# S4QX11.net
KiCad netlist of a schematic drawn in EAGLE
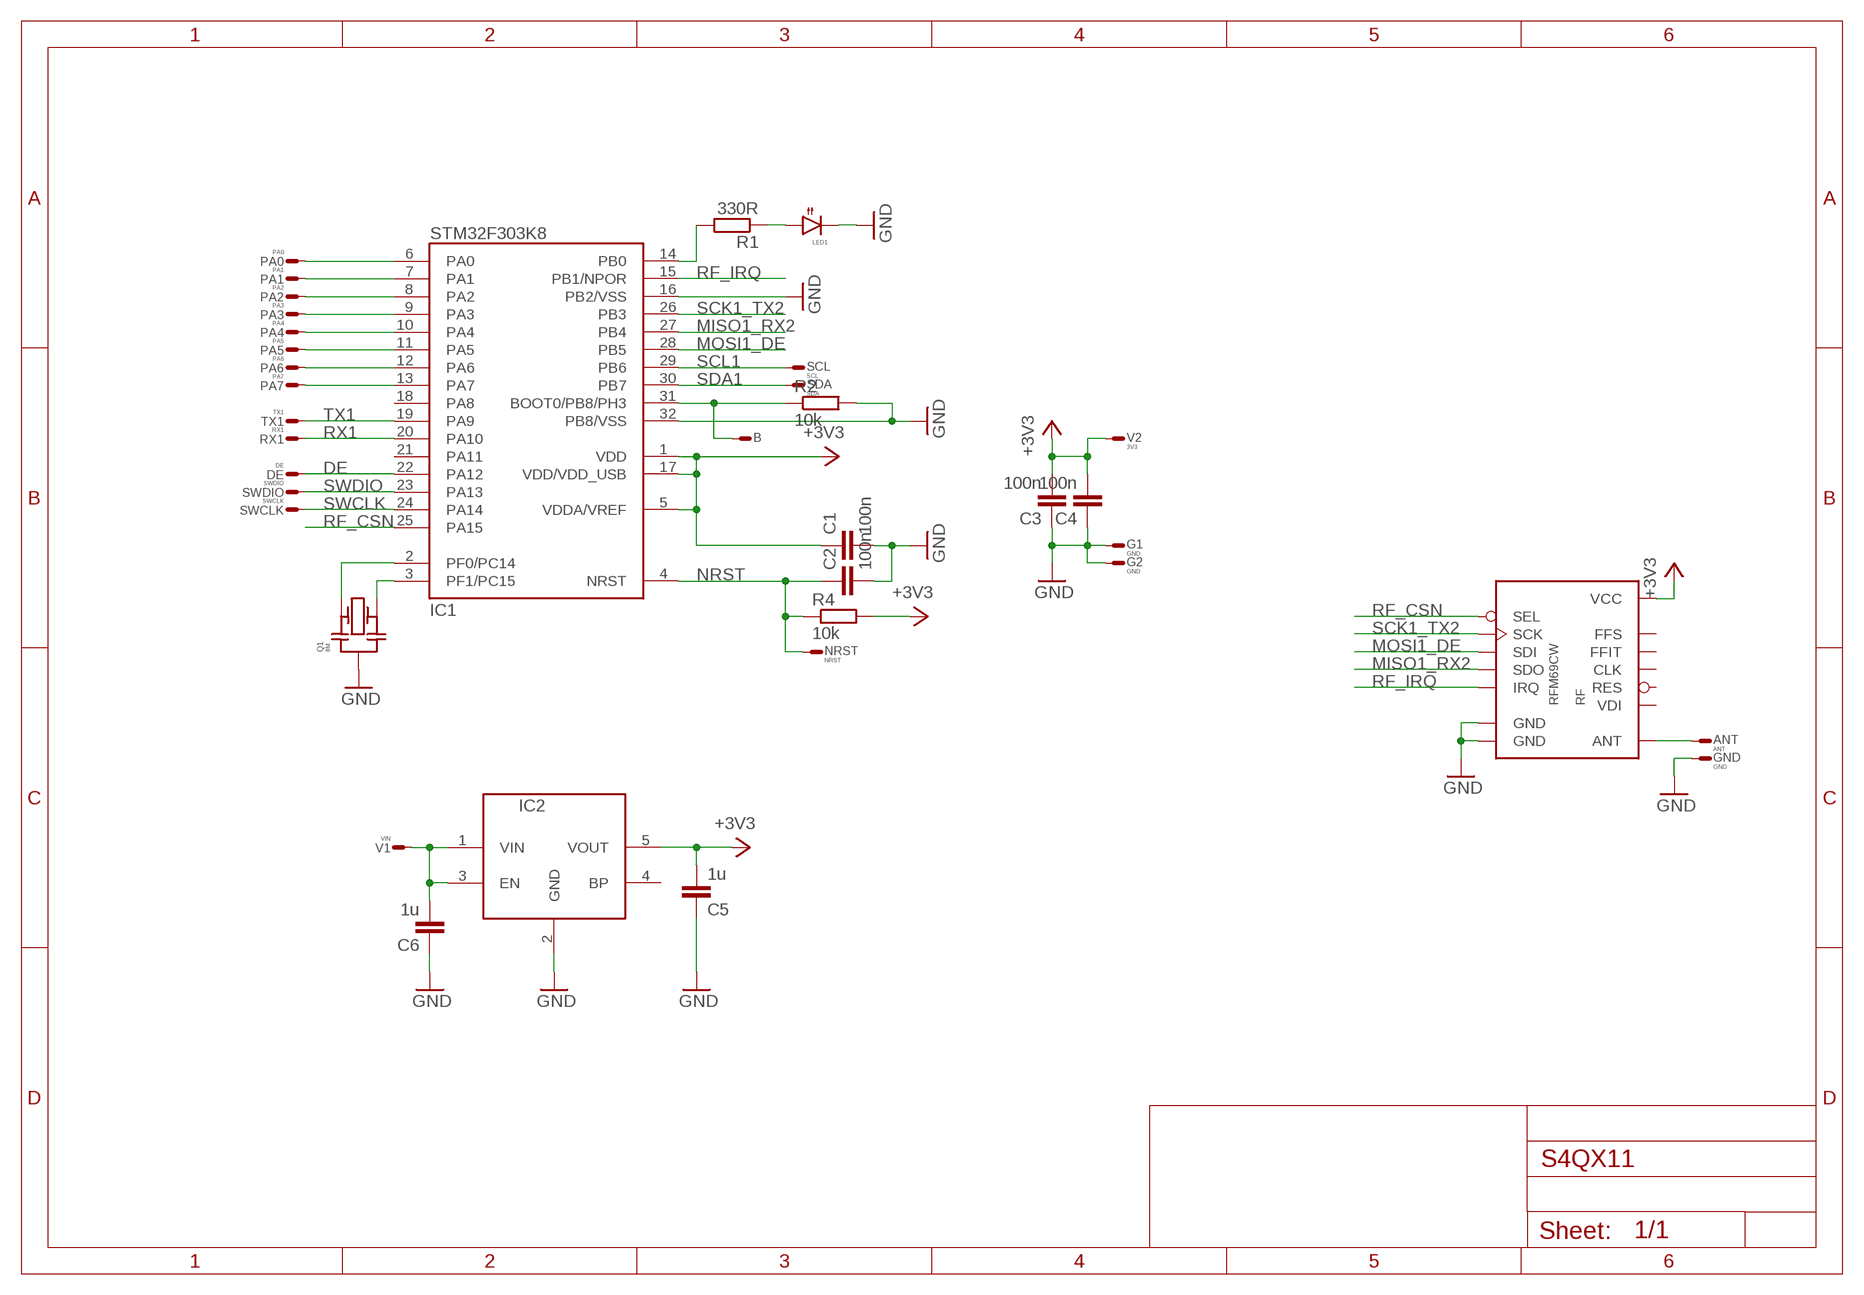
[diagram p0: schematic, sheet 1]

(export (version "E")
  (design (tool "Eeschema 10.0.6"))
  (components
    (comp (ref "ANT")
      (value "ANT")
      (footprint "eagle-import:T1.6_0.9")
      (libsource (lib "eagle-import") (part "WIREPADT1.6/0.9"))
    )
    (comp (ref "B")
      (value "WIREPADR")
      (footprint "eagle-import:S1.27R")
      (libsource (lib "eagle-import") (part "WIREPADR"))
    )
    (comp (ref "C1")
      (value "100n")
      (footprint "eagle-import:0603")
      (libsource (lib "eagle-import") (part "C0603"))
    )
    (comp (ref "C2")
      (value "100n")
      (footprint "eagle-import:0603")
      (libsource (lib "eagle-import") (part "C0603"))
    )
    (comp (ref "C3")
      (value "100n")
      (footprint "eagle-import:0603")
      (libsource (lib "eagle-import") (part "C0603"))
    )
    (comp (ref "C4")
      (value "100n")
      (footprint "eagle-import:0603")
      (libsource (lib "eagle-import") (part "C0603"))
    )
    (comp (ref "C5")
      (value "1u")
      (footprint "eagle-import:0603")
      (libsource (lib "eagle-import") (part "C0603"))
    )
    (comp (ref "C6")
      (value "1u")
      (footprint "eagle-import:0603")
      (libsource (lib "eagle-import") (part "C0603"))
    )
    (comp (ref "DE")
      (value "DE")
      (footprint "eagle-import:T1.6_0.9")
      (libsource (lib "eagle-import") (part "WIREPADT1.6/0.9"))
    )
    (comp (ref "G1")
      (value "GND")
      (footprint "eagle-import:T1.6_0.9")
      (libsource (lib "eagle-import") (part "WIREPADT1.6/0.9"))
    )
    (comp (ref "G2")
      (value "GND")
      (footprint "eagle-import:T1.6_0.9")
      (libsource (lib "eagle-import") (part "WIREPADT1.6/0.9"))
    )
    (comp (ref "GND")
      (value "GND")
      (footprint "eagle-import:T1.6_0.9")
      (libsource (lib "eagle-import") (part "WIREPADT1.6/0.9"))
    )
    (comp (ref "IC1")
      (value "STM32F303K8")
      (footprint "eagle-import:LQFP32-7X7")
      (libsource (lib "eagle-import") (part "STM32_LQFP32"))
    )
    (comp (ref "IC2")
      (value "LDO")
      (footprint "eagle-import:SOT23-5")
      (libsource (lib "eagle-import") (part "LDO"))
    )
    (comp (ref "LED1")
      (value "LED1206")
      (footprint "eagle-import:1206")
      (libsource (lib "eagle-import") (part "LED1206"))
    )
    (comp (ref "NRST")
      (value "NRST")
      (footprint "eagle-import:T1.6_0.9")
      (libsource (lib "eagle-import") (part "WIREPADT1.6/0.9"))
    )
    (comp (ref "PA0")
      (value "PA0")
      (footprint "eagle-import:T1.6_0.9")
      (libsource (lib "eagle-import") (part "WIREPADT1.6/0.9"))
    )
    (comp (ref "PA1")
      (value "PA1")
      (footprint "eagle-import:T1.6_0.9")
      (libsource (lib "eagle-import") (part "WIREPADT1.6/0.9"))
    )
    (comp (ref "PA2")
      (value "PA2")
      (footprint "eagle-import:T1.6_0.9")
      (libsource (lib "eagle-import") (part "WIREPADT1.6/0.9"))
    )
    (comp (ref "PA3")
      (value "PA3")
      (footprint "eagle-import:T1.6_0.9")
      (libsource (lib "eagle-import") (part "WIREPADT1.6/0.9"))
    )
    (comp (ref "PA4")
      (value "PA4")
      (footprint "eagle-import:T1.6_0.9")
      (libsource (lib "eagle-import") (part "WIREPADT1.6/0.9"))
    )
    (comp (ref "PA5")
      (value "PA5")
      (footprint "eagle-import:T1.6_0.9")
      (libsource (lib "eagle-import") (part "WIREPADT1.6/0.9"))
    )
    (comp (ref "PA6")
      (value "PA6")
      (footprint "eagle-import:T1.6_0.9")
      (libsource (lib "eagle-import") (part "WIREPADT1.6/0.9"))
    )
    (comp (ref "PA7")
      (value "PA7")
      (footprint "eagle-import:T1.6_0.9")
      (libsource (lib "eagle-import") (part "WIREPADT1.6/0.9"))
    )
    (comp (ref "Q1")
      (value "8M")
      (footprint "eagle-import:CSTCE")
      (libsource (lib "eagle-import") (part "QRCE"))
    )
    (comp (ref "R1")
      (value "330R")
      (footprint "eagle-import:0603")
      (libsource (lib "eagle-import") (part "R0603"))
    )
    (comp (ref "R2")
      (value "10k")
      (footprint "eagle-import:0603")
      (libsource (lib "eagle-import") (part "R0603"))
    )
    (comp (ref "R4")
      (value "10k")
      (footprint "eagle-import:0603")
      (libsource (lib "eagle-import") (part "R0603"))
    )
    (comp (ref "RF")
      (value "RFM69CW")
      (footprint "eagle-import:RFM12B")
      (libsource (lib "eagle-import") (part "RFM12BS1-868-"))
    )
    (comp (ref "RX1")
      (value "RX1")
      (footprint "eagle-import:T1.6_0.9")
      (libsource (lib "eagle-import") (part "WIREPADT1.6/0.9"))
    )
    (comp (ref "SCL")
      (value "SCL")
      (footprint "eagle-import:T1.6_0.9")
      (libsource (lib "eagle-import") (part "WIREPADT1.6/0.9"))
    )
    (comp (ref "SDA")
      (value "SDA")
      (footprint "eagle-import:T1.6_0.9")
      (libsource (lib "eagle-import") (part "WIREPADT1.6/0.9"))
    )
    (comp (ref "SWCLK")
      (value "SWCLK")
      (footprint "eagle-import:T1.6_0.9")
      (libsource (lib "eagle-import") (part "WIREPADT1.6/0.9"))
    )
    (comp (ref "SWDIO")
      (value "SWDIO")
      (footprint "eagle-import:T1.6_0.9")
      (libsource (lib "eagle-import") (part "WIREPADT1.6/0.9"))
    )
    (comp (ref "TX1")
      (value "TX1")
      (footprint "eagle-import:T1.6_0.9")
      (libsource (lib "eagle-import") (part "WIREPADT1.6/0.9"))
    )
    (comp (ref "V1")
      (value "VIN")
      (footprint "eagle-import:T1.6_0.9")
      (libsource (lib "eagle-import") (part "WIREPADT1.6/0.9"))
    )
    (comp (ref "V2")
      (value "3V3")
      (footprint "eagle-import:T1.6_0.9")
      (libsource (lib "eagle-import") (part "WIREPADT1.6/0.9"))
    )
  )
  (nets
    (net (code "1") (name "+3V3") (class "Default")
      (node (ref "C1") (pin "1") (pinfunction "1_1") (pintype "passive"))
      (node (ref "C3") (pin "2") (pinfunction "2_2") (pintype "passive"))
      (node (ref "C4") (pin "2") (pinfunction "2_2") (pintype "passive"))
      (node (ref "C5") (pin "2") (pinfunction "2_2") (pintype "passive"))
      (node (ref "IC1") (pin "1") (pinfunction "VDD_1") (pintype "bidirectional"))
      (node (ref "IC1") (pin "17") (pinfunction "VDD/VDD_USB_17") (pintype "bidirectional"))
      (node (ref "IC1") (pin "5") (pinfunction "VDDA/VREF_5") (pintype "bidirectional"))
      (node (ref "IC2") (pin "5") (pinfunction "VOUT_5") (pintype "bidirectional"))
      (node (ref "R4") (pin "2") (pinfunction "2_2") (pintype "passive"))
      (node (ref "RF") (pin "VDD") (pinfunction "VCC_VDD") (pintype "power_in"))
      (node (ref "V2") (pin "1") (pinfunction "S_1") (pintype "passive"))
    )
    (net (code "2") (name "/DE") (class "Default")
      (node (ref "DE") (pin "1") (pinfunction "S_1") (pintype "passive"))
      (node (ref "IC1") (pin "22") (pinfunction "PA12_22") (pintype "bidirectional"))
    )
    (net (code "3") (name "/MISO1_RX2") (class "Default")
      (node (ref "IC1") (pin "27") (pinfunction "PB4_27") (pintype "bidirectional"))
      (node (ref "RF") (pin "SDO") (pinfunction "SDO_SDO") (pintype "output"))
    )
    (net (code "4") (name "/MOSI1_DE") (class "Default")
      (node (ref "IC1") (pin "28") (pinfunction "PB5_28") (pintype "bidirectional"))
      (node (ref "RF") (pin "SDI") (pinfunction "SDI_SDI") (pintype "input"))
    )
    (net (code "5") (name "/NRST") (class "Default")
      (node (ref "C2") (pin "1") (pinfunction "1_1") (pintype "passive"))
      (node (ref "IC1") (pin "4") (pinfunction "NRST_4") (pintype "bidirectional"))
      (node (ref "NRST") (pin "1") (pinfunction "S_1") (pintype "passive"))
      (node (ref "R4") (pin "1") (pinfunction "1_1") (pintype "passive"))
    )
    (net (code "6") (name "/RF_CSN") (class "Default")
      (node (ref "IC1") (pin "25") (pinfunction "PA15_25") (pintype "bidirectional"))
      (node (ref "RF") (pin "SEL") (pinfunction "SEL_SEL") (pintype "input"))
    )
    (net (code "7") (name "/RF_IRQ") (class "Default")
      (node (ref "IC1") (pin "15") (pinfunction "PB1/NPOR_15") (pintype "bidirectional"))
      (node (ref "RF") (pin "IRQ") (pinfunction "IRQ_IRQ") (pintype "open_collector"))
    )
    (net (code "8") (name "/RX1") (class "Default")
      (node (ref "IC1") (pin "20") (pinfunction "PA10_20") (pintype "bidirectional"))
      (node (ref "RX1") (pin "1") (pinfunction "S_1") (pintype "passive"))
    )
    (net (code "9") (name "/SCK1_TX2") (class "Default")
      (node (ref "IC1") (pin "26") (pinfunction "PB3_26") (pintype "bidirectional"))
      (node (ref "RF") (pin "SCK") (pinfunction "SCK_SCK") (pintype "input"))
    )
    (net (code "10") (name "/SCL1") (class "Default")
      (node (ref "IC1") (pin "29") (pinfunction "PB6_29") (pintype "bidirectional"))
      (node (ref "SCL") (pin "1") (pinfunction "S_1") (pintype "passive"))
    )
    (net (code "11") (name "/SDA1") (class "Default")
      (node (ref "IC1") (pin "30") (pinfunction "PB7_30") (pintype "bidirectional"))
      (node (ref "SDA") (pin "1") (pinfunction "S_1") (pintype "passive"))
    )
    (net (code "12") (name "/SWCLK") (class "Default")
      (node (ref "IC1") (pin "24") (pinfunction "PA14_24") (pintype "bidirectional"))
      (node (ref "SWCLK") (pin "1") (pinfunction "S_1") (pintype "passive"))
    )
    (net (code "13") (name "/SWDIO") (class "Default")
      (node (ref "IC1") (pin "23") (pinfunction "PA13_23") (pintype "bidirectional"))
      (node (ref "SWDIO") (pin "1") (pinfunction "S_1") (pintype "passive"))
    )
    (net (code "14") (name "/TX1") (class "Default")
      (node (ref "IC1") (pin "19") (pinfunction "PA9_19") (pintype "bidirectional"))
      (node (ref "TX1") (pin "1") (pinfunction "S_1") (pintype "passive"))
    )
    (net (code "15") (name "GND") (class "Default")
      (node (ref "C1") (pin "2") (pinfunction "2_2") (pintype "passive"))
      (node (ref "C2") (pin "2") (pinfunction "2_2") (pintype "passive"))
      (node (ref "C3") (pin "1") (pinfunction "1_1") (pintype "passive"))
      (node (ref "C4") (pin "1") (pinfunction "1_1") (pintype "passive"))
      (node (ref "C5") (pin "1") (pinfunction "1_1") (pintype "passive"))
      (node (ref "C6") (pin "1") (pinfunction "1_1") (pintype "passive"))
      (node (ref "G1") (pin "1") (pinfunction "S_1") (pintype "passive"))
      (node (ref "G2") (pin "1") (pinfunction "S_1") (pintype "passive"))
      (node (ref "GND") (pin "1") (pinfunction "S_1") (pintype "passive"))
      (node (ref "IC1") (pin "16") (pinfunction "PB2/VSS_16") (pintype "bidirectional"))
      (node (ref "IC1") (pin "32") (pinfunction "PB8/VSS_32") (pintype "bidirectional"))
      (node (ref "IC2") (pin "2") (pinfunction "GND_2") (pintype "bidirectional"))
      (node (ref "LED1") (pin "2") (pinfunction "C_2") (pintype "bidirectional"))
      (node (ref "Q1") (pin "G") (pinfunction "M_G") (pintype "passive"))
      (node (ref "R2") (pin "2") (pinfunction "2_2") (pintype "passive"))
      (node (ref "RF") (pin "GND") (pinfunction "GND_GND") (pintype "power_in"))
      (node (ref "RF") (pin "GND@1") (pinfunction "GND_GND@1") (pintype "power_in"))
    )
    (net (code "16") (name "Net-(ANT-S)") (class "Default")
      (node (ref "ANT") (pin "1") (pinfunction "S_1") (pintype "passive"))
      (node (ref "RF") (pin "ANT") (pinfunction "ANT_ANT") (pintype "passive"))
    )
    (net (code "17") (name "Net-(B-S)") (class "Default")
      (node (ref "B") (pin "1") (pinfunction "S_1") (pintype "passive"))
      (node (ref "IC1") (pin "31") (pinfunction "BOOT0/PB8/PH3_31") (pintype "bidirectional"))
      (node (ref "R2") (pin "1") (pinfunction "1_1") (pintype "passive"))
    )
    (net (code "18") (name "Net-(IC1-PA0)") (class "Default")
      (node (ref "IC1") (pin "6") (pinfunction "PA0_6") (pintype "bidirectional"))
      (node (ref "PA0") (pin "1") (pinfunction "S_1") (pintype "passive"))
    )
    (net (code "19") (name "Net-(IC1-PA1)") (class "Default")
      (node (ref "IC1") (pin "7") (pinfunction "PA1_7") (pintype "bidirectional"))
      (node (ref "PA1") (pin "1") (pinfunction "S_1") (pintype "passive"))
    )
    (net (code "20") (name "Net-(IC1-PA2)") (class "Default")
      (node (ref "IC1") (pin "8") (pinfunction "PA2_8") (pintype "bidirectional"))
      (node (ref "PA2") (pin "1") (pinfunction "S_1") (pintype "passive"))
    )
    (net (code "21") (name "Net-(IC1-PA3)") (class "Default")
      (node (ref "IC1") (pin "9") (pinfunction "PA3_9") (pintype "bidirectional"))
      (node (ref "PA3") (pin "1") (pinfunction "S_1") (pintype "passive"))
    )
    (net (code "22") (name "Net-(IC1-PA4)") (class "Default")
      (node (ref "IC1") (pin "10") (pinfunction "PA4_10") (pintype "bidirectional"))
      (node (ref "PA4") (pin "1") (pinfunction "S_1") (pintype "passive"))
    )
    (net (code "23") (name "Net-(IC1-PA5)") (class "Default")
      (node (ref "IC1") (pin "11") (pinfunction "PA5_11") (pintype "bidirectional"))
      (node (ref "PA5") (pin "1") (pinfunction "S_1") (pintype "passive"))
    )
    (net (code "24") (name "Net-(IC1-PA6)") (class "Default")
      (node (ref "IC1") (pin "12") (pinfunction "PA6_12") (pintype "bidirectional"))
      (node (ref "PA6") (pin "1") (pinfunction "S_1") (pintype "passive"))
    )
    (net (code "25") (name "Net-(IC1-PA7)") (class "Default")
      (node (ref "IC1") (pin "13") (pinfunction "PA7_13") (pintype "bidirectional"))
      (node (ref "PA7") (pin "1") (pinfunction "S_1") (pintype "passive"))
    )
    (net (code "26") (name "Net-(IC1-PB0)") (class "Default")
      (node (ref "IC1") (pin "14") (pinfunction "PB0_14") (pintype "bidirectional"))
      (node (ref "R1") (pin "2") (pinfunction "2_2") (pintype "passive"))
    )
    (net (code "27") (name "Net-(IC1-PF0{slash}PC14)") (class "Default")
      (node (ref "IC1") (pin "2") (pinfunction "PF0/PC14_2") (pintype "bidirectional"))
      (node (ref "Q1") (pin "A") (pinfunction "1_A") (pintype "passive"))
    )
    (net (code "28") (name "Net-(IC1-PF1{slash}PC15)") (class "Default")
      (node (ref "IC1") (pin "3") (pinfunction "PF1/PC15_3") (pintype "bidirectional"))
      (node (ref "Q1") (pin "B") (pinfunction "2_B") (pintype "passive"))
    )
    (net (code "29") (name "Net-(IC2-EN)") (class "Default")
      (node (ref "C6") (pin "2") (pinfunction "2_2") (pintype "passive"))
      (node (ref "IC2") (pin "1") (pinfunction "VIN_1") (pintype "bidirectional"))
      (node (ref "IC2") (pin "3") (pinfunction "EN_3") (pintype "bidirectional"))
      (node (ref "V1") (pin "1") (pinfunction "S_1") (pintype "passive"))
    )
    (net (code "30") (name "Net-(LED1-A)") (class "Default")
      (node (ref "LED1") (pin "1") (pinfunction "A_1") (pintype "bidirectional"))
      (node (ref "R1") (pin "1") (pinfunction "1_1") (pintype "passive"))
    )
    (net (code "31") (name "unconnected-(IC1-PA8-Pad18)") (class "Default")
      (node (ref "IC1") (pin "18") (pinfunction "PA8_18") (pintype "bidirectional"))
    )
    (net (code "32") (name "unconnected-(IC1-PA11-Pad21)") (class "Default")
      (node (ref "IC1") (pin "21") (pinfunction "PA11_21") (pintype "bidirectional"))
    )
    (net (code "33") (name "unconnected-(IC2-BP-Pad4)") (class "Default")
      (node (ref "IC2") (pin "4") (pinfunction "BP_4") (pintype "bidirectional"))
    )
    (net (code "34") (name "unconnected-(RF-FFIT-PadCFIL)") (class "Default")
      (node (ref "RF") (pin "CFIL") (pinfunction "FFIT_CFIL") (pintype "bidirectional"))
    )
    (net (code "35") (name "unconnected-(RF-PadCLK)") (class "Default")
      (node (ref "RF") (pin "CLK") (pinfunction "CLK_CLK") (pintype "output"))
    )
    (net (code "36") (name "unconnected-(RF-PadFFS)") (class "Default")
      (node (ref "RF") (pin "FFS") (pinfunction "FFS_FFS") (pintype "bidirectional"))
    )
    (net (code "37") (name "unconnected-(RF-RES-Pad{slash}RES)") (class "Default")
      (node (ref "RF") (pin "/RES") (pinfunction "RES_/RES") (pintype "bidirectional"))
    )
    (net (code "38") (name "unconnected-(RF-VDI-PadINT)") (class "Default")
      (node (ref "RF") (pin "INT") (pinfunction "VDI_INT") (pintype "bidirectional"))
    )
  )
)
